# terra_o_verde_placa_perfurada_sem_pluvio.net
KiCad netlist of a schematic drawn in EAGLE
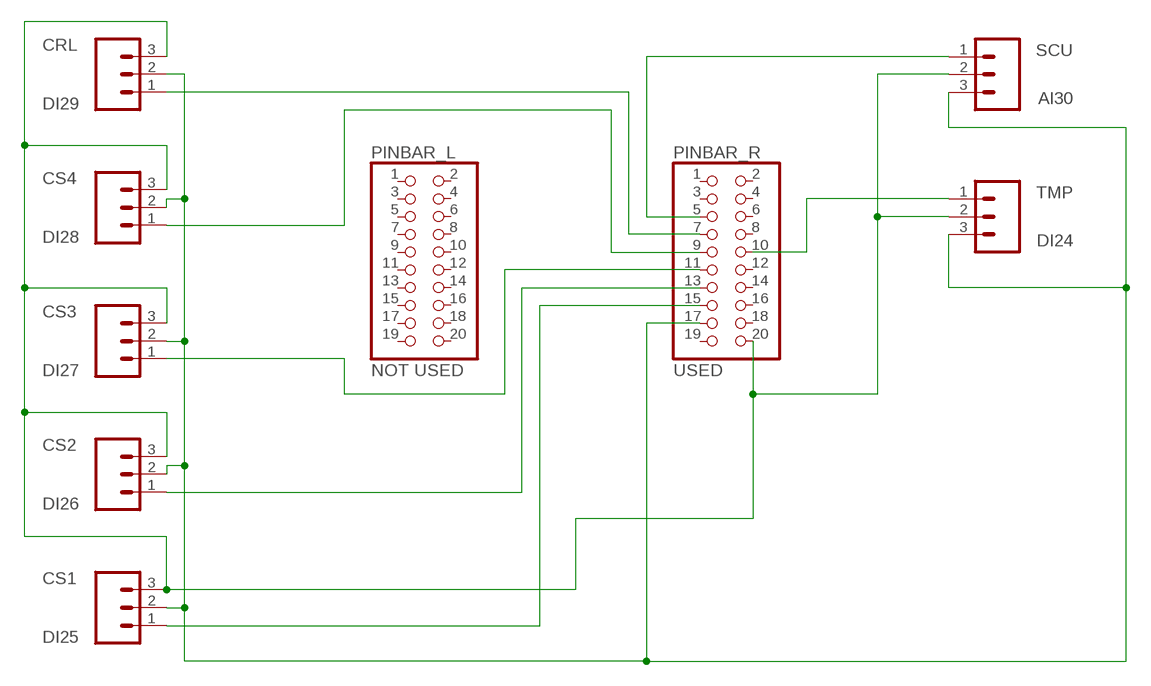
[diagram p0: schematic, sheet 1]

(export (version "E")
  (design (tool "Eeschema 10.0.6"))
  (components
    (comp (ref "CRL")
      (value "DI29")
      (footprint "eagle-import:03P")
      (libsource (lib "eagle-import") (part "M03"))
    )
    (comp (ref "CS1")
      (value "DI25")
      (footprint "eagle-import:03P")
      (libsource (lib "eagle-import") (part "M03"))
    )
    (comp (ref "CS2")
      (value "DI26")
      (footprint "eagle-import:03P")
      (libsource (lib "eagle-import") (part "M03"))
    )
    (comp (ref "CS3")
      (value "DI27")
      (footprint "eagle-import:03P")
      (libsource (lib "eagle-import") (part "M03"))
    )
    (comp (ref "CS4")
      (value "DI28")
      (footprint "eagle-import:03P")
      (libsource (lib "eagle-import") (part "M03"))
    )
    (comp (ref "PINBAR_L")
      (value "NOT USED")
      (footprint "eagle-import:2X10")
      (libsource (lib "eagle-import") (part "PINHD-2X10"))
    )
    (comp (ref "PINBAR_R")
      (value "USED")
      (footprint "eagle-import:2X10")
      (libsource (lib "eagle-import") (part "PINHD-2X10"))
    )
    (comp (ref "SCU")
      (value "AI30")
      (footprint "eagle-import:03P")
      (libsource (lib "eagle-import") (part "M03"))
    )
    (comp (ref "TMP")
      (value "DI24")
      (footprint "eagle-import:03P")
      (libsource (lib "eagle-import") (part "M03"))
    )
  )
  (nets
    (net (code "1") (name "Net-(CRL-Pad1)") (class "Default")
      (node (ref "CRL") (pin "1") (pinfunction "1_1") (pintype "passive"))
      (node (ref "PINBAR_R") (pin "7") (pinfunction "7_7") (pintype "passive"))
    )
    (net (code "2") (name "Net-(CRL-Pad2)") (class "Default")
      (node (ref "CRL") (pin "2") (pinfunction "2_2") (pintype "passive"))
      (node (ref "CS1") (pin "2") (pinfunction "2_2") (pintype "passive"))
      (node (ref "CS2") (pin "2") (pinfunction "2_2") (pintype "passive"))
      (node (ref "CS3") (pin "2") (pinfunction "2_2") (pintype "passive"))
      (node (ref "CS4") (pin "2") (pinfunction "2_2") (pintype "passive"))
      (node (ref "PINBAR_R") (pin "17") (pinfunction "17_17") (pintype "passive"))
      (node (ref "SCU") (pin "3") (pinfunction "3_3") (pintype "passive"))
      (node (ref "TMP") (pin "3") (pinfunction "3_3") (pintype "passive"))
    )
    (net (code "3") (name "Net-(CRL-Pad3)") (class "Default")
      (node (ref "CRL") (pin "3") (pinfunction "3_3") (pintype "passive"))
      (node (ref "CS1") (pin "3") (pinfunction "3_3") (pintype "passive"))
      (node (ref "CS2") (pin "3") (pinfunction "3_3") (pintype "passive"))
      (node (ref "CS3") (pin "3") (pinfunction "3_3") (pintype "passive"))
      (node (ref "CS4") (pin "3") (pinfunction "3_3") (pintype "passive"))
      (node (ref "PINBAR_R") (pin "20") (pinfunction "20_20") (pintype "passive"))
      (node (ref "SCU") (pin "2") (pinfunction "2_2") (pintype "passive"))
      (node (ref "TMP") (pin "2") (pinfunction "2_2") (pintype "passive"))
    )
    (net (code "4") (name "Net-(CS1-Pad1)") (class "Default")
      (node (ref "CS1") (pin "1") (pinfunction "1_1") (pintype "passive"))
      (node (ref "PINBAR_R") (pin "15") (pinfunction "15_15") (pintype "passive"))
    )
    (net (code "5") (name "Net-(CS2-Pad1)") (class "Default")
      (node (ref "CS2") (pin "1") (pinfunction "1_1") (pintype "passive"))
      (node (ref "PINBAR_R") (pin "13") (pinfunction "13_13") (pintype "passive"))
    )
    (net (code "6") (name "Net-(CS3-Pad1)") (class "Default")
      (node (ref "CS3") (pin "1") (pinfunction "1_1") (pintype "passive"))
      (node (ref "PINBAR_R") (pin "11") (pinfunction "11_11") (pintype "passive"))
    )
    (net (code "7") (name "Net-(CS4-Pad1)") (class "Default")
      (node (ref "CS4") (pin "1") (pinfunction "1_1") (pintype "passive"))
      (node (ref "PINBAR_R") (pin "9") (pinfunction "9_9") (pintype "passive"))
    )
    (net (code "8") (name "Net-(PINBAR_R-Pad5)") (class "Default")
      (node (ref "PINBAR_R") (pin "5") (pinfunction "5_5") (pintype "passive"))
      (node (ref "SCU") (pin "1") (pinfunction "1_1") (pintype "passive"))
    )
    (net (code "9") (name "Net-(PINBAR_R-Pad10)") (class "Default")
      (node (ref "PINBAR_R") (pin "10") (pinfunction "10_10") (pintype "passive"))
      (node (ref "TMP") (pin "1") (pinfunction "1_1") (pintype "passive"))
    )
    (net (code "10") (name "unconnected-(PINBAR_L-Pad1)") (class "Default")
      (node (ref "PINBAR_L") (pin "1") (pinfunction "1_1") (pintype "passive"))
    )
    (net (code "11") (name "unconnected-(PINBAR_L-Pad2)") (class "Default")
      (node (ref "PINBAR_L") (pin "2") (pinfunction "2_2") (pintype "passive"))
    )
    (net (code "12") (name "unconnected-(PINBAR_L-Pad3)") (class "Default")
      (node (ref "PINBAR_L") (pin "3") (pinfunction "3_3") (pintype "passive"))
    )
    (net (code "13") (name "unconnected-(PINBAR_L-Pad4)") (class "Default")
      (node (ref "PINBAR_L") (pin "4") (pinfunction "4_4") (pintype "passive"))
    )
    (net (code "14") (name "unconnected-(PINBAR_L-Pad5)") (class "Default")
      (node (ref "PINBAR_L") (pin "5") (pinfunction "5_5") (pintype "passive"))
    )
    (net (code "15") (name "unconnected-(PINBAR_L-Pad6)") (class "Default")
      (node (ref "PINBAR_L") (pin "6") (pinfunction "6_6") (pintype "passive"))
    )
    (net (code "16") (name "unconnected-(PINBAR_L-Pad7)") (class "Default")
      (node (ref "PINBAR_L") (pin "7") (pinfunction "7_7") (pintype "passive"))
    )
    (net (code "17") (name "unconnected-(PINBAR_L-Pad8)") (class "Default")
      (node (ref "PINBAR_L") (pin "8") (pinfunction "8_8") (pintype "passive"))
    )
    (net (code "18") (name "unconnected-(PINBAR_L-Pad9)") (class "Default")
      (node (ref "PINBAR_L") (pin "9") (pinfunction "9_9") (pintype "passive"))
    )
    (net (code "19") (name "unconnected-(PINBAR_L-Pad10)") (class "Default")
      (node (ref "PINBAR_L") (pin "10") (pinfunction "10_10") (pintype "passive"))
    )
    (net (code "20") (name "unconnected-(PINBAR_L-Pad11)") (class "Default")
      (node (ref "PINBAR_L") (pin "11") (pinfunction "11_11") (pintype "passive"))
    )
    (net (code "21") (name "unconnected-(PINBAR_L-Pad12)") (class "Default")
      (node (ref "PINBAR_L") (pin "12") (pinfunction "12_12") (pintype "passive"))
    )
    (net (code "22") (name "unconnected-(PINBAR_L-Pad13)") (class "Default")
      (node (ref "PINBAR_L") (pin "13") (pinfunction "13_13") (pintype "passive"))
    )
    (net (code "23") (name "unconnected-(PINBAR_L-Pad14)") (class "Default")
      (node (ref "PINBAR_L") (pin "14") (pinfunction "14_14") (pintype "passive"))
    )
    (net (code "24") (name "unconnected-(PINBAR_L-Pad15)") (class "Default")
      (node (ref "PINBAR_L") (pin "15") (pinfunction "15_15") (pintype "passive"))
    )
    (net (code "25") (name "unconnected-(PINBAR_L-Pad16)") (class "Default")
      (node (ref "PINBAR_L") (pin "16") (pinfunction "16_16") (pintype "passive"))
    )
    (net (code "26") (name "unconnected-(PINBAR_L-Pad17)") (class "Default")
      (node (ref "PINBAR_L") (pin "17") (pinfunction "17_17") (pintype "passive"))
    )
    (net (code "27") (name "unconnected-(PINBAR_L-Pad18)") (class "Default")
      (node (ref "PINBAR_L") (pin "18") (pinfunction "18_18") (pintype "passive"))
    )
    (net (code "28") (name "unconnected-(PINBAR_L-Pad19)") (class "Default")
      (node (ref "PINBAR_L") (pin "19") (pinfunction "19_19") (pintype "passive"))
    )
    (net (code "29") (name "unconnected-(PINBAR_L-Pad20)") (class "Default")
      (node (ref "PINBAR_L") (pin "20") (pinfunction "20_20") (pintype "passive"))
    )
    (net (code "30") (name "unconnected-(PINBAR_R-Pad1)") (class "Default")
      (node (ref "PINBAR_R") (pin "1") (pinfunction "1_1") (pintype "passive"))
    )
    (net (code "31") (name "unconnected-(PINBAR_R-Pad2)") (class "Default")
      (node (ref "PINBAR_R") (pin "2") (pinfunction "2_2") (pintype "passive"))
    )
    (net (code "32") (name "unconnected-(PINBAR_R-Pad3)") (class "Default")
      (node (ref "PINBAR_R") (pin "3") (pinfunction "3_3") (pintype "passive"))
    )
    (net (code "33") (name "unconnected-(PINBAR_R-Pad4)") (class "Default")
      (node (ref "PINBAR_R") (pin "4") (pinfunction "4_4") (pintype "passive"))
    )
    (net (code "34") (name "unconnected-(PINBAR_R-Pad6)") (class "Default")
      (node (ref "PINBAR_R") (pin "6") (pinfunction "6_6") (pintype "passive"))
    )
    (net (code "35") (name "unconnected-(PINBAR_R-Pad8)") (class "Default")
      (node (ref "PINBAR_R") (pin "8") (pinfunction "8_8") (pintype "passive"))
    )
    (net (code "36") (name "unconnected-(PINBAR_R-Pad12)") (class "Default")
      (node (ref "PINBAR_R") (pin "12") (pinfunction "12_12") (pintype "passive"))
    )
    (net (code "37") (name "unconnected-(PINBAR_R-Pad14)") (class "Default")
      (node (ref "PINBAR_R") (pin "14") (pinfunction "14_14") (pintype "passive"))
    )
    (net (code "38") (name "unconnected-(PINBAR_R-Pad16)") (class "Default")
      (node (ref "PINBAR_R") (pin "16") (pinfunction "16_16") (pintype "passive"))
    )
    (net (code "39") (name "unconnected-(PINBAR_R-Pad18)") (class "Default")
      (node (ref "PINBAR_R") (pin "18") (pinfunction "18_18") (pintype "passive"))
    )
    (net (code "40") (name "unconnected-(PINBAR_R-Pad19)") (class "Default")
      (node (ref "PINBAR_R") (pin "19") (pinfunction "19_19") (pintype "passive"))
    )
  )
)
